# Differential_Amp.net
KiCad netlist of a schematic drawn in Altium Designer
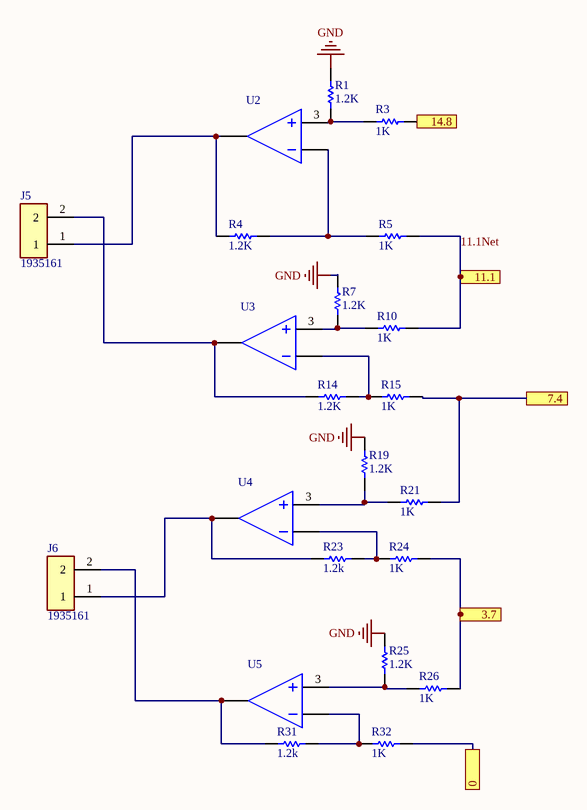
[diagram p0: Differential_Amp.SchDoc]

(export (version "E")
  (design (tool "Eeschema 10.0.6"))
  (components
    (comp (ref "J5")
      (value "1935161")
      (footprint "PHOENIX_1935161")
      (description "Conn Terminal Blocks 2 POS 5mm Solder ST Thru-Hole 16A")
      (fields (field (name "MF") "{'manufacturer': u'Phoenix Contact'}"))
      (libsource (lib "1935161") (part "1935161"))
    )
    (comp (ref "J6")
      (value "1935161")
      (footprint "PHOENIX_1935161")
      (description "Conn Terminal Blocks 2 POS 5mm Solder ST Thru-Hole 16A")
      (fields (field (name "MF") "{'manufacturer': u'Phoenix Contact'}"))
      (libsource (lib "1935161") (part "1935161"))
    )
    (comp (ref "R1")
      (value "1.2K")
      (footprint "0805")
      (description "Resistor")
      (libsource (lib "Simulation Generic Components") (part "Resistor"))
    )
    (comp (ref "R3")
      (value "1K")
      (footprint "0805")
      (description "Resistor")
      (libsource (lib "Simulation Generic Components") (part "Resistor"))
    )
    (comp (ref "R4")
      (value "1.2K")
      (footprint "0805")
      (description "Resistor")
      (libsource (lib "Simulation Generic Components") (part "Resistor"))
    )
    (comp (ref "R5")
      (value "1K")
      (footprint "0805")
      (description "Resistor")
      (libsource (lib "Simulation Generic Components") (part "Resistor"))
    )
    (comp (ref "R7")
      (value "1.2K")
      (footprint "0805")
      (description "Resistor")
      (libsource (lib "Simulation Generic Components") (part "Resistor"))
    )
    (comp (ref "R10")
      (value "1K")
      (footprint "0805")
      (description "Resistor")
      (libsource (lib "Simulation Generic Components") (part "Resistor"))
    )
    (comp (ref "R14")
      (value "1.2K")
      (footprint "0805")
      (description "Resistor")
      (libsource (lib "Simulation Generic Components") (part "Resistor"))
    )
    (comp (ref "R15")
      (value "1K")
      (footprint "0805")
      (description "Resistor")
      (libsource (lib "Simulation Generic Components") (part "Resistor"))
    )
    (comp (ref "R19")
      (value "1.2K")
      (footprint "0805")
      (description "Resistor")
      (libsource (lib "Simulation Generic Components") (part "Resistor"))
    )
    (comp (ref "R21")
      (value "1K")
      (footprint "0805")
      (description "Resistor")
      (libsource (lib "Simulation Generic Components") (part "Resistor"))
    )
    (comp (ref "R23")
      (value "1.2k")
      (footprint "0805")
      (description "Resistor")
      (libsource (lib "Simulation Generic Components") (part "Resistor"))
    )
    (comp (ref "R24")
      (value "1K")
      (footprint "0805")
      (description "Resistor")
      (libsource (lib "Simulation Generic Components") (part "Resistor"))
    )
    (comp (ref "R25")
      (value "1.2K")
      (footprint "0805")
      (description "Resistor")
      (libsource (lib "Simulation Generic Components") (part "Resistor"))
    )
    (comp (ref "R26")
      (value "1K")
      (footprint "0805")
      (description "Resistor")
      (libsource (lib "Simulation Generic Components") (part "Resistor"))
    )
    (comp (ref "R31")
      (value "1.2k")
      (footprint "0805")
      (description "Resistor")
      (libsource (lib "Simulation Generic Components") (part "Resistor"))
    )
    (comp (ref "R32")
      (value "1K")
      (footprint "0805")
      (description "Resistor")
      (libsource (lib "Simulation Generic Components") (part "Resistor"))
    )
    (comp (ref "U2")
      (value "Ideal Operational Amplifier")
      (footprint "SOT95P280X110-6N")
      (libsource (lib "Simulation Generic Components") (part "OpAmp"))
    )
    (comp (ref "U3")
      (value "Ideal Operational Amplifier")
      (footprint "SOT95P280X110-6N")
      (libsource (lib "Simulation Generic Components") (part "OpAmp"))
    )
    (comp (ref "U4")
      (value "Ideal Operational Amplifier")
      (footprint "SOT95P280X110-6N")
      (libsource (lib "Simulation Generic Components") (part "OpAmp"))
    )
    (comp (ref "U5")
      (value "Ideal Operational Amplifier")
      (footprint "SOT95P280X110-6N")
      (libsource (lib "Simulation Generic Components") (part "OpAmp"))
    )
  )
  (nets
    (net (code "1") (name "/0") (class "Default")
      (node (ref "R32") (pin "1") (pinfunction "1_1") (pintype "passive"))
    )
    (net (code "2") (name "/3.7") (class "Default")
      (node (ref "R24") (pin "1") (pinfunction "1_1") (pintype "passive"))
      (node (ref "R26") (pin "1") (pinfunction "1_1") (pintype "passive"))
    )
    (net (code "3") (name "/7.4") (class "Default")
      (node (ref "R15") (pin "1") (pinfunction "1_1") (pintype "passive"))
      (node (ref "R21") (pin "1") (pinfunction "1_1") (pintype "passive"))
    )
    (net (code "4") (name "/11.1Net") (class "Default")
      (node (ref "R10") (pin "1") (pinfunction "1_1") (pintype "passive"))
      (node (ref "R5") (pin "1") (pinfunction "1_1") (pintype "passive"))
    )
    (net (code "5") (name "/14.8") (class "Default")
      (node (ref "R3") (pin "1") (pinfunction "1_1") (pintype "passive"))
    )
    (net (code "6") (name "GND") (class "Default")
      (node (ref "R1") (pin "1") (pinfunction "1_1") (pintype "passive"))
      (node (ref "R19") (pin "1") (pinfunction "1_1") (pintype "passive"))
      (node (ref "R25") (pin "1") (pinfunction "1_1") (pintype "passive"))
      (node (ref "R7") (pin "1") (pinfunction "1_1") (pintype "passive"))
    )
    (net (code "7") (name "Net-(U2-IN+)") (class "Default")
      (node (ref "R1") (pin "2") (pinfunction "2_2") (pintype "passive"))
      (node (ref "R3") (pin "2") (pinfunction "2_2") (pintype "passive"))
      (node (ref "U2") (pin "3") (pinfunction "IN+_3") (pintype "passive"))
    )
    (net (code "8") (name "Net-(U2-IN-)") (class "Default")
      (node (ref "R4") (pin "1") (pinfunction "1_1") (pintype "passive"))
      (node (ref "R5") (pin "2") (pinfunction "2_2") (pintype "passive"))
      (node (ref "U2") (pin "4") (pinfunction "IN-_4") (pintype "passive"))
    )
    (net (code "9") (name "Net-(U2-OUT)") (class "Default")
      (node (ref "J5") (pin "1") (pinfunction "1_1") (pintype "passive"))
      (node (ref "R4") (pin "2") (pinfunction "2_2") (pintype "passive"))
      (node (ref "U2") (pin "1") (pinfunction "OUT_1") (pintype "passive"))
    )
    (net (code "10") (name "Net-(U3-IN+)") (class "Default")
      (node (ref "R10") (pin "2") (pinfunction "2_2") (pintype "passive"))
      (node (ref "R7") (pin "2") (pinfunction "2_2") (pintype "passive"))
      (node (ref "U3") (pin "3") (pinfunction "IN+_3") (pintype "passive"))
    )
    (net (code "11") (name "Net-(U3-IN-)") (class "Default")
      (node (ref "R14") (pin "1") (pinfunction "1_1") (pintype "passive"))
      (node (ref "R15") (pin "2") (pinfunction "2_2") (pintype "passive"))
      (node (ref "U3") (pin "4") (pinfunction "IN-_4") (pintype "passive"))
    )
    (net (code "12") (name "Net-(U3-OUT)") (class "Default")
      (node (ref "J5") (pin "2") (pinfunction "2_2") (pintype "passive"))
      (node (ref "R14") (pin "2") (pinfunction "2_2") (pintype "passive"))
      (node (ref "U3") (pin "1") (pinfunction "OUT_1") (pintype "passive"))
    )
    (net (code "13") (name "Net-(U4-IN+)") (class "Default")
      (node (ref "R19") (pin "2") (pinfunction "2_2") (pintype "passive"))
      (node (ref "R21") (pin "2") (pinfunction "2_2") (pintype "passive"))
      (node (ref "U4") (pin "3") (pinfunction "IN+_3") (pintype "passive"))
    )
    (net (code "14") (name "Net-(U4-IN-)") (class "Default")
      (node (ref "R23") (pin "1") (pinfunction "1_1") (pintype "passive"))
      (node (ref "R24") (pin "2") (pinfunction "2_2") (pintype "passive"))
      (node (ref "U4") (pin "4") (pinfunction "IN-_4") (pintype "passive"))
    )
    (net (code "15") (name "Net-(U4-OUT)") (class "Default")
      (node (ref "J6") (pin "1") (pinfunction "1_1") (pintype "passive"))
      (node (ref "R23") (pin "2") (pinfunction "2_2") (pintype "passive"))
      (node (ref "U4") (pin "1") (pinfunction "OUT_1") (pintype "passive"))
    )
    (net (code "16") (name "Net-(U5-IN+)") (class "Default")
      (node (ref "R25") (pin "2") (pinfunction "2_2") (pintype "passive"))
      (node (ref "R26") (pin "2") (pinfunction "2_2") (pintype "passive"))
      (node (ref "U5") (pin "3") (pinfunction "IN+_3") (pintype "passive"))
    )
    (net (code "17") (name "Net-(U5-IN-)") (class "Default")
      (node (ref "R31") (pin "1") (pinfunction "1_1") (pintype "passive"))
      (node (ref "R32") (pin "2") (pinfunction "2_2") (pintype "passive"))
      (node (ref "U5") (pin "4") (pinfunction "IN-_4") (pintype "passive"))
    )
    (net (code "18") (name "Net-(U5-OUT)") (class "Default")
      (node (ref "J6") (pin "2") (pinfunction "2_2") (pintype "passive"))
      (node (ref "R31") (pin "2") (pinfunction "2_2") (pintype "passive"))
      (node (ref "U5") (pin "1") (pinfunction "OUT_1") (pintype "passive"))
    )
  )
)
